# class_b.net
KiCad netlist of a schematic drawn in EAGLE
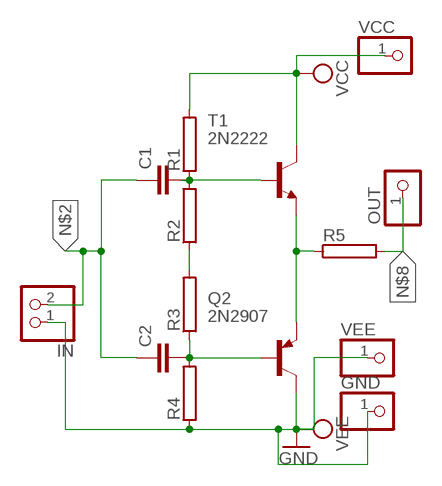
[diagram p0: schematic, sheet 1]

(export (version "E")
  (design (tool "Eeschema 10.0.6"))
  (components
    (comp (ref "C1")
      (value "C2,5-3")
      (footprint "eagle-import:C2.5-3")
      (libsource (lib "eagle-import") (part "C2,5-3"))
    )
    (comp (ref "C2")
      (value "C2,5-3")
      (footprint "eagle-import:C2.5-3")
      (libsource (lib "eagle-import") (part "C2,5-3"))
    )
    (comp (ref "GND")
      (value "PINHD-1X1")
      (footprint "eagle-import:1X01")
      (libsource (lib "eagle-import") (part "PINHD-1X1"))
    )
    (comp (ref "IN")
      (value "PINHD-1X2")
      (footprint "eagle-import:1X02")
      (libsource (lib "eagle-import") (part "PINHD-1X2"))
    )
    (comp (ref "OUT")
      (value "PINHD-1X1")
      (footprint "eagle-import:1X01")
      (libsource (lib "eagle-import") (part "PINHD-1X1"))
    )
    (comp (ref "Q2")
      (value "2N2907")
      (footprint "eagle-import:TO18")
      (libsource (lib "eagle-import") (part "2N2907"))
    )
    (comp (ref "R1")
      (value "RAC01")
      (footprint "eagle-import:AC01")
      (libsource (lib "eagle-import") (part "RAC01"))
    )
    (comp (ref "R2")
      (value "RAC01")
      (footprint "eagle-import:AC01")
      (libsource (lib "eagle-import") (part "RAC01"))
    )
    (comp (ref "R3")
      (value "RAC01")
      (footprint "eagle-import:AC01")
      (libsource (lib "eagle-import") (part "RAC01"))
    )
    (comp (ref "R4")
      (value "RAC01")
      (footprint "eagle-import:AC01")
      (libsource (lib "eagle-import") (part "RAC01"))
    )
    (comp (ref "R5")
      (value "RAC01")
      (footprint "eagle-import:AC01")
      (libsource (lib "eagle-import") (part "RAC01"))
    )
    (comp (ref "T1")
      (value "2N2222")
      (footprint "eagle-import:TO18")
      (libsource (lib "eagle-import") (part "2N2222"))
    )
    (comp (ref "VCC")
      (value "PINHD-1X1")
      (footprint "eagle-import:1X01")
      (libsource (lib "eagle-import") (part "PINHD-1X1"))
    )
    (comp (ref "VEE")
      (value "PINHD-1X1")
      (footprint "eagle-import:1X01")
      (libsource (lib "eagle-import") (part "PINHD-1X1"))
    )
  )
  (nets
    (net (code "1") (name "GND") (class "Default")
      (node (ref "GND") (pin "1") (pinfunction "1_1") (pintype "passive"))
      (node (ref "IN") (pin "1") (pinfunction "1_1") (pintype "passive"))
      (node (ref "Q2") (pin "3") (pinfunction "C_3") (pintype "passive"))
      (node (ref "R4") (pin "1") (pinfunction "1_1") (pintype "passive"))
      (node (ref "VEE") (pin "1") (pinfunction "1_1") (pintype "passive"))
    )
    (net (code "2") (name "N$2") (class "Default")
      (node (ref "C1") (pin "1") (pinfunction "1_1") (pintype "passive"))
      (node (ref "C2") (pin "1") (pinfunction "1_1") (pintype "passive"))
      (node (ref "IN") (pin "2") (pinfunction "2_2") (pintype "passive"))
    )
    (net (code "3") (name "N$8") (class "Default")
      (node (ref "OUT") (pin "1") (pinfunction "1_1") (pintype "passive"))
      (node (ref "R5") (pin "2") (pinfunction "2_2") (pintype "passive"))
    )
    (net (code "4") (name "Net-(Q2-B)") (class "Default")
      (node (ref "C2") (pin "2") (pinfunction "2_2") (pintype "passive"))
      (node (ref "Q2") (pin "2") (pinfunction "B_2") (pintype "passive"))
      (node (ref "R3") (pin "1") (pinfunction "1_1") (pintype "passive"))
      (node (ref "R4") (pin "2") (pinfunction "2_2") (pintype "passive"))
    )
    (net (code "5") (name "Net-(Q2-E)") (class "Default")
      (node (ref "Q2") (pin "1") (pinfunction "E_1") (pintype "passive"))
      (node (ref "R5") (pin "1") (pinfunction "1_1") (pintype "passive"))
      (node (ref "T1") (pin "1") (pinfunction "E_1") (pintype "passive"))
    )
    (net (code "6") (name "Net-(R2-Pad1)") (class "Default")
      (node (ref "R2") (pin "1") (pinfunction "1_1") (pintype "passive"))
      (node (ref "R3") (pin "2") (pinfunction "2_2") (pintype "passive"))
    )
    (net (code "7") (name "Net-(T1-B)") (class "Default")
      (node (ref "C1") (pin "2") (pinfunction "2_2") (pintype "passive"))
      (node (ref "R1") (pin "1") (pinfunction "1_1") (pintype "passive"))
      (node (ref "R2") (pin "2") (pinfunction "2_2") (pintype "passive"))
      (node (ref "T1") (pin "2") (pinfunction "B_2") (pintype "passive"))
    )
    (net (code "8") (name "VCC") (class "Default")
      (node (ref "R1") (pin "2") (pinfunction "2_2") (pintype "passive"))
      (node (ref "T1") (pin "3") (pinfunction "C_3") (pintype "passive"))
      (node (ref "VCC") (pin "1") (pinfunction "1_1") (pintype "passive"))
    )
  )
)
